# I2C_Multiplexers.net
KiCad netlist of a schematic drawn in Altium Designer
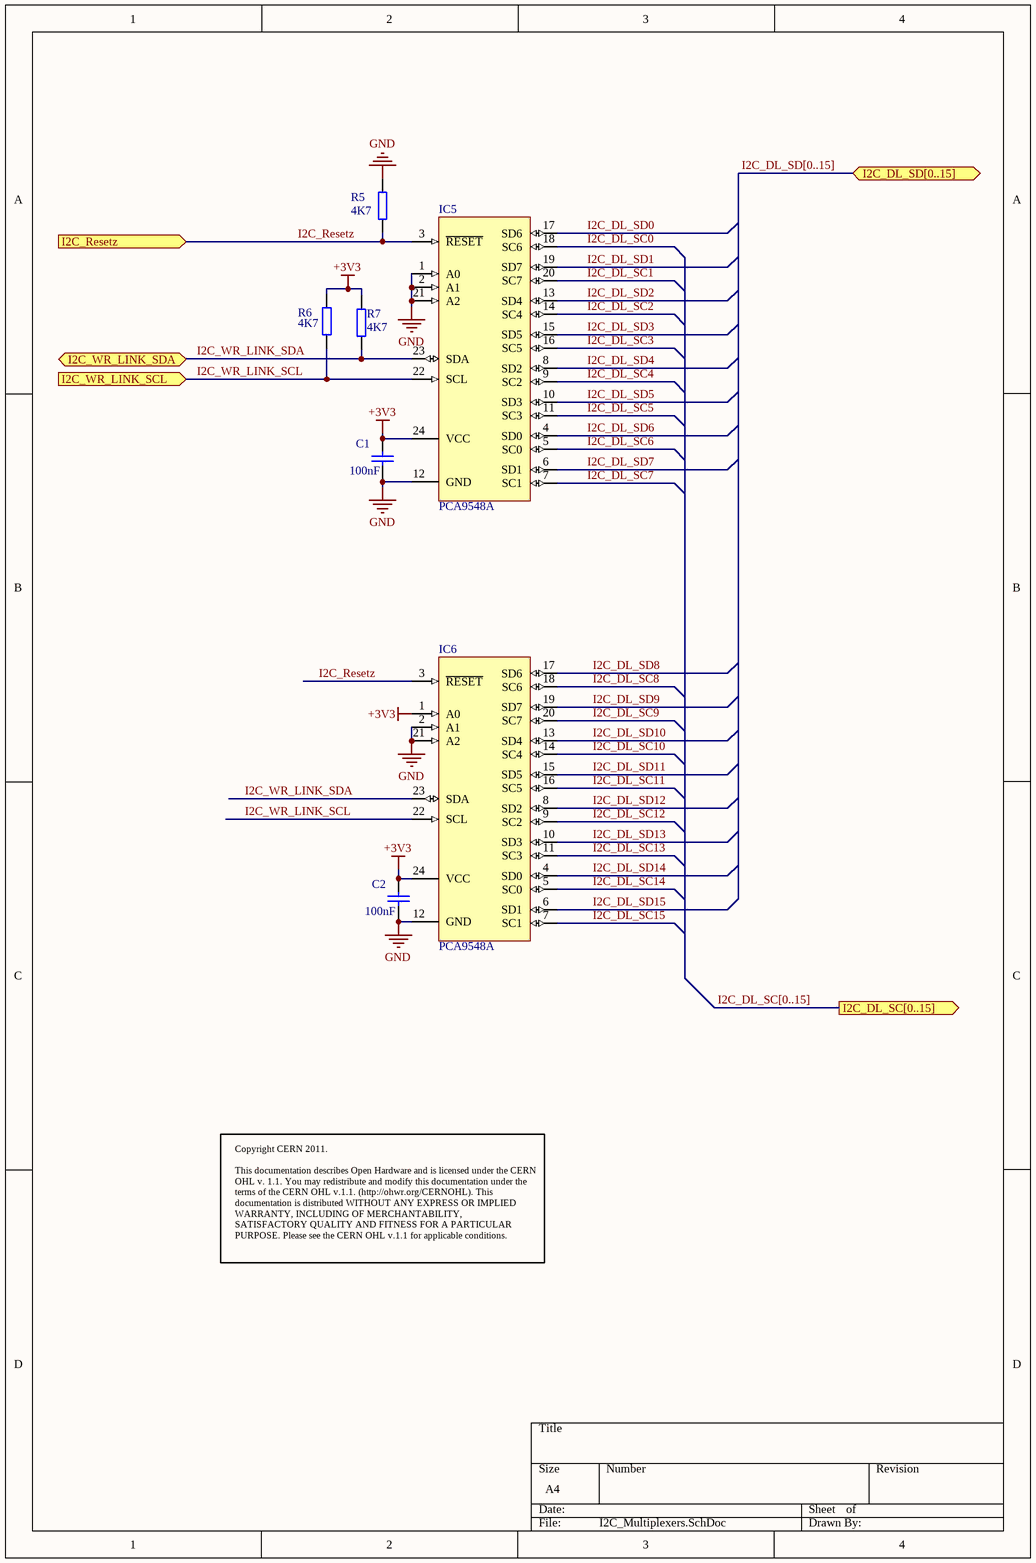
[diagram p0: I2C_Multiplexers.SchDoc]

(export (version "E")
  (design (tool "Eeschema 10.0.6"))
  (components
    (comp (ref "C1")
      (value "100nF")
      (footprint "CC1608-0603")
      (description "Capacitor")
      (fields
        (field (name "TOLERANCE") "±10%")
        (field (name "VOLTAGE") "16V")
        (field (name "PUBLISHER") "Altium Limited")
      )
      (libsource (lib "wr_switch") (part "Cap"))
    )
    (comp (ref "C2")
      (value "100nF")
      (footprint "CC1608-0603")
      (description "Capacitor")
      (fields
        (field (name "TOLERANCE") "±10%")
        (field (name "VOLTAGE") "16V")
        (field (name "PUBLISHER") "Altium Limited")
      )
      (libsource (lib "wr_switch") (part "Cap"))
    )
    (comp (ref "IC5")
      (value "PCA9548A")
      (footprint "SOP65P640X120-24N")
      (description "8-channel 2C-bus switch with reset")
      (libsource (lib "wr_switch") (part "PCA9548A"))
    )
    (comp (ref "IC6")
      (value "PCA9548A")
      (footprint "SOP65P640X120-24N")
      (description "8-channel 2C-bus switch with reset")
      (libsource (lib "wr_switch") (part "PCA9548A"))
    )
    (comp (ref "R5")
      (value "4K7")
      (footprint "0603")
      (description "SMD Resistor")
      (fields (field (name "TOLERANCE") "±1%"))
      (libsource (lib "wr_switch") (part "RES_SMD"))
    )
    (comp (ref "R6")
      (value "4K7")
      (footprint "0603")
      (description "SMD Resistor")
      (fields (field (name "TOLERANCE") "±1%"))
      (libsource (lib "wr_switch") (part "RES_SMD"))
    )
    (comp (ref "R7")
      (value "4K7")
      (footprint "0603")
      (description "SMD Resistor")
      (fields (field (name "TOLERANCE") "±1%"))
      (libsource (lib "wr_switch") (part "RES_SMD"))
    )
  )
  (nets
    (net (code "1") (name "+3V3") (class "Default")
      (node (ref "C1") (pin "2") (pinfunction "2_2") (pintype "passive"))
      (node (ref "C2") (pin "2") (pinfunction "2_2") (pintype "passive"))
      (node (ref "IC5") (pin "24") (pinfunction "VCC_24") (pintype "power_in"))
      (node (ref "IC6") (pin "1") (pinfunction "A0_1") (pintype "input"))
      (node (ref "IC6") (pin "24") (pinfunction "VCC_24") (pintype "power_in"))
      (node (ref "R6") (pin "1") (pinfunction "1_1") (pintype "passive"))
      (node (ref "R7") (pin "1") (pinfunction "1_1") (pintype "passive"))
    )
    (net (code "2") (name "/I2C_DL_SC0") (class "Default")
      (node (ref "IC5") (pin "18") (pinfunction "SC6_18") (pintype "bidirectional"))
    )
    (net (code "3") (name "/I2C_DL_SC1") (class "Default")
      (node (ref "IC5") (pin "20") (pinfunction "SC7_20") (pintype "bidirectional"))
    )
    (net (code "4") (name "/I2C_DL_SC2") (class "Default")
      (node (ref "IC5") (pin "14") (pinfunction "SC4_14") (pintype "bidirectional"))
    )
    (net (code "5") (name "/I2C_DL_SC3") (class "Default")
      (node (ref "IC5") (pin "16") (pinfunction "SC5_16") (pintype "bidirectional"))
    )
    (net (code "6") (name "/I2C_DL_SC4") (class "Default")
      (node (ref "IC5") (pin "9") (pinfunction "SC2_9") (pintype "bidirectional"))
    )
    (net (code "7") (name "/I2C_DL_SC5") (class "Default")
      (node (ref "IC5") (pin "11") (pinfunction "SC3_11") (pintype "bidirectional"))
    )
    (net (code "8") (name "/I2C_DL_SC6") (class "Default")
      (node (ref "IC5") (pin "5") (pinfunction "SC0_5") (pintype "bidirectional"))
    )
    (net (code "9") (name "/I2C_DL_SC7") (class "Default")
      (node (ref "IC5") (pin "7") (pinfunction "SC1_7") (pintype "bidirectional"))
    )
    (net (code "10") (name "/I2C_DL_SC8") (class "Default")
      (node (ref "IC6") (pin "18") (pinfunction "SC6_18") (pintype "bidirectional"))
    )
    (net (code "11") (name "/I2C_DL_SC9") (class "Default")
      (node (ref "IC6") (pin "20") (pinfunction "SC7_20") (pintype "bidirectional"))
    )
    (net (code "12") (name "/I2C_DL_SC10") (class "Default")
      (node (ref "IC6") (pin "14") (pinfunction "SC4_14") (pintype "bidirectional"))
    )
    (net (code "13") (name "/I2C_DL_SC11") (class "Default")
      (node (ref "IC6") (pin "16") (pinfunction "SC5_16") (pintype "bidirectional"))
    )
    (net (code "14") (name "/I2C_DL_SC12") (class "Default")
      (node (ref "IC6") (pin "9") (pinfunction "SC2_9") (pintype "bidirectional"))
    )
    (net (code "15") (name "/I2C_DL_SC13") (class "Default")
      (node (ref "IC6") (pin "11") (pinfunction "SC3_11") (pintype "bidirectional"))
    )
    (net (code "16") (name "/I2C_DL_SC14") (class "Default")
      (node (ref "IC6") (pin "5") (pinfunction "SC0_5") (pintype "bidirectional"))
    )
    (net (code "17") (name "/I2C_DL_SC15") (class "Default")
      (node (ref "IC6") (pin "7") (pinfunction "SC1_7") (pintype "bidirectional"))
    )
    (net (code "19") (name "/I2C_DL_SD0") (class "Default")
      (node (ref "IC5") (pin "17") (pinfunction "SD6_17") (pintype "bidirectional"))
    )
    (net (code "20") (name "/I2C_DL_SD1") (class "Default")
      (node (ref "IC5") (pin "19") (pinfunction "SD7_19") (pintype "bidirectional"))
    )
    (net (code "21") (name "/I2C_DL_SD2") (class "Default")
      (node (ref "IC5") (pin "13") (pinfunction "SD4_13") (pintype "bidirectional"))
    )
    (net (code "22") (name "/I2C_DL_SD3") (class "Default")
      (node (ref "IC5") (pin "15") (pinfunction "SD5_15") (pintype "bidirectional"))
    )
    (net (code "23") (name "/I2C_DL_SD4") (class "Default")
      (node (ref "IC5") (pin "8") (pinfunction "SD2_8") (pintype "bidirectional"))
    )
    (net (code "24") (name "/I2C_DL_SD5") (class "Default")
      (node (ref "IC5") (pin "10") (pinfunction "SD3_10") (pintype "bidirectional"))
    )
    (net (code "25") (name "/I2C_DL_SD6") (class "Default")
      (node (ref "IC5") (pin "4") (pinfunction "SD0_4") (pintype "bidirectional"))
    )
    (net (code "26") (name "/I2C_DL_SD7") (class "Default")
      (node (ref "IC5") (pin "6") (pinfunction "SD1_6") (pintype "bidirectional"))
    )
    (net (code "27") (name "/I2C_DL_SD8") (class "Default")
      (node (ref "IC6") (pin "17") (pinfunction "SD6_17") (pintype "bidirectional"))
    )
    (net (code "28") (name "/I2C_DL_SD9") (class "Default")
      (node (ref "IC6") (pin "19") (pinfunction "SD7_19") (pintype "bidirectional"))
    )
    (net (code "29") (name "/I2C_DL_SD10") (class "Default")
      (node (ref "IC6") (pin "13") (pinfunction "SD4_13") (pintype "bidirectional"))
    )
    (net (code "30") (name "/I2C_DL_SD11") (class "Default")
      (node (ref "IC6") (pin "15") (pinfunction "SD5_15") (pintype "bidirectional"))
    )
    (net (code "31") (name "/I2C_DL_SD12") (class "Default")
      (node (ref "IC6") (pin "8") (pinfunction "SD2_8") (pintype "bidirectional"))
    )
    (net (code "32") (name "/I2C_DL_SD13") (class "Default")
      (node (ref "IC6") (pin "10") (pinfunction "SD3_10") (pintype "bidirectional"))
    )
    (net (code "33") (name "/I2C_DL_SD14") (class "Default")
      (node (ref "IC6") (pin "4") (pinfunction "SD0_4") (pintype "bidirectional"))
    )
    (net (code "34") (name "/I2C_DL_SD15") (class "Default")
      (node (ref "IC6") (pin "6") (pinfunction "SD1_6") (pintype "bidirectional"))
    )
    (net (code "36") (name "/I2C_Resetz") (class "Default")
      (node (ref "IC5") (pin "3") (pinfunction "~{RESET}_3") (pintype "input"))
      (node (ref "IC6") (pin "3") (pinfunction "~{RESET}_3") (pintype "input"))
      (node (ref "R5") (pin "1") (pinfunction "1_1") (pintype "passive"))
    )
    (net (code "37") (name "/I2C_WR_LINK_SCL") (class "Default")
      (node (ref "IC5") (pin "22") (pinfunction "SCL_22") (pintype "input"))
      (node (ref "IC6") (pin "22") (pinfunction "SCL_22") (pintype "input"))
      (node (ref "R6") (pin "2") (pinfunction "2_2") (pintype "passive"))
    )
    (net (code "38") (name "/I2C_WR_LINK_SDA") (class "Default")
      (node (ref "IC5") (pin "23") (pinfunction "SDA_23") (pintype "bidirectional"))
      (node (ref "IC6") (pin "23") (pinfunction "SDA_23") (pintype "bidirectional"))
      (node (ref "R7") (pin "2") (pinfunction "2_2") (pintype "passive"))
    )
    (net (code "39") (name "GND") (class "Default")
      (node (ref "C1") (pin "1") (pinfunction "1_1") (pintype "passive"))
      (node (ref "C2") (pin "1") (pinfunction "1_1") (pintype "passive"))
      (node (ref "IC5") (pin "1") (pinfunction "A0_1") (pintype "input"))
      (node (ref "IC5") (pin "12") (pinfunction "GND_12") (pintype "power_in"))
      (node (ref "IC5") (pin "2") (pinfunction "A1_2") (pintype "input"))
      (node (ref "IC5") (pin "21") (pinfunction "A2_21") (pintype "input"))
      (node (ref "IC6") (pin "12") (pinfunction "GND_12") (pintype "power_in"))
      (node (ref "IC6") (pin "2") (pinfunction "A1_2") (pintype "input"))
      (node (ref "IC6") (pin "21") (pinfunction "A2_21") (pintype "input"))
      (node (ref "R5") (pin "2") (pinfunction "2_2") (pintype "passive"))
    )
  )
)
